# RTB2k_Pattern_Gen_Adapter.net
KiCad netlist of a schematic drawn in Altium Designer
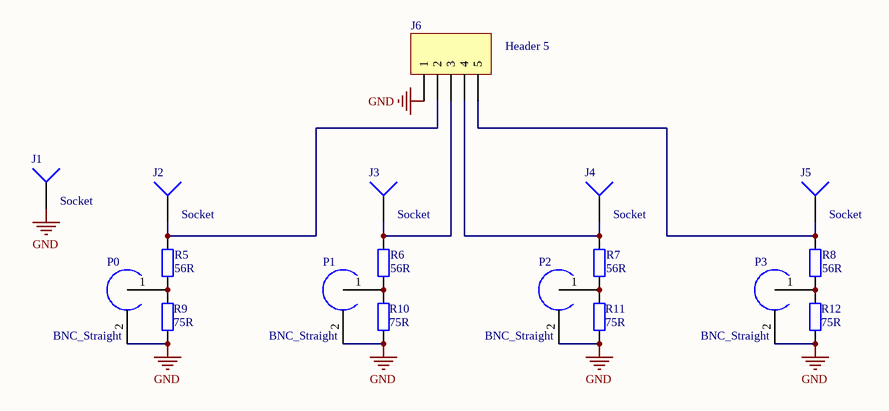
[diagram p0: RTB2k Pattern Gen Adapter.SchDoc]

(export (version "E")
  (design (tool "Eeschema 10.0.6"))
  (components
    (comp (ref "J1")
      (value "Socket")
      (footprint "PIN1")
      (fields (field (name "PUBLISHER") "Altium Limited"))
      (libsource (lib "Miscellaneous Connectors") (part "Socket"))
    )
    (comp (ref "J2")
      (value "Socket")
      (footprint "PIN1")
      (fields (field (name "PUBLISHER") "Altium Limited"))
      (libsource (lib "Miscellaneous Connectors") (part "Socket"))
    )
    (comp (ref "J3")
      (value "Socket")
      (footprint "PIN1")
      (fields (field (name "PUBLISHER") "Altium Limited"))
      (libsource (lib "Miscellaneous Connectors") (part "Socket"))
    )
    (comp (ref "J4")
      (value "Socket")
      (footprint "PIN1")
      (fields (field (name "PUBLISHER") "Altium Limited"))
      (libsource (lib "Miscellaneous Connectors") (part "Socket"))
    )
    (comp (ref "J5")
      (value "Socket")
      (footprint "PIN1")
      (fields (field (name "PUBLISHER") "Altium Limited"))
      (libsource (lib "Miscellaneous Connectors") (part "Socket"))
    )
    (comp (ref "J6")
      (value "Header 5")
      (footprint "HDR1X5")
      (description "Header, 5-Pin")
      (fields (field (name "PUBLISHER") "Altium Limited"))
      (libsource (lib "Miscellaneous Connectors") (part "Header 5"))
    )
    (comp (ref "P0")
      (value "BNC_Straight")
      (footprint "BNC_Straight")
      (description "BNC Connector (Straight)")
      (libsource (lib "TV_Altium_library") (part "BNC_Straight"))
    )
    (comp (ref "P1")
      (value "BNC_Straight")
      (footprint "BNC_Straight")
      (description "BNC Connector (Straight)")
      (libsource (lib "TV_Altium_library") (part "BNC_Straight"))
    )
    (comp (ref "P2")
      (value "BNC_Straight")
      (footprint "BNC_Straight")
      (description "BNC Connector (Straight)")
      (libsource (lib "TV_Altium_library") (part "BNC_Straight"))
    )
    (comp (ref "P3")
      (value "BNC_Straight")
      (footprint "BNC_Straight")
      (description "BNC Connector (Straight)")
      (libsource (lib "TV_Altium_library") (part "BNC_Straight"))
    )
    (comp (ref "R5")
      (value "56R")
      (footprint "0805R")
      (libsource (lib "TV_Altium_library") (part "Resistor"))
    )
    (comp (ref "R6")
      (value "56R")
      (footprint "0805R")
      (libsource (lib "TV_Altium_library") (part "Resistor"))
    )
    (comp (ref "R7")
      (value "56R")
      (footprint "0805R")
      (libsource (lib "TV_Altium_library") (part "Resistor"))
    )
    (comp (ref "R8")
      (value "56R")
      (footprint "0805R")
      (libsource (lib "TV_Altium_library") (part "Resistor"))
    )
    (comp (ref "R9") (value "75R") (footprint "0805R") (libsource (lib "") (part "Resistor_1")))
    (comp (ref "R10") (value "75R") (footprint "0805R") (libsource (lib "") (part "Resistor_1")))
    (comp (ref "R11") (value "75R") (footprint "0805R") (libsource (lib "") (part "Resistor_1")))
    (comp (ref "R12") (value "75R") (footprint "0805R") (libsource (lib "") (part "Resistor_1")))
  )
  (nets
    (net (code "1") (name "GND") (class "Default")
      (node (ref "J1") (pin "1") (pinfunction "1_1") (pintype "passive"))
      (node (ref "J6") (pin "1") (pinfunction "1_1") (pintype "passive"))
      (node (ref "P0") (pin "2") (pinfunction "Shield_2") (pintype "passive"))
      (node (ref "P1") (pin "2") (pinfunction "Shield_2") (pintype "passive"))
      (node (ref "P2") (pin "2") (pinfunction "Shield_2") (pintype "passive"))
      (node (ref "P3") (pin "2") (pinfunction "Shield_2") (pintype "passive"))
      (node (ref "R10") (pin "2") (pinfunction "2_2") (pintype "passive"))
      (node (ref "R11") (pin "2") (pinfunction "2_2") (pintype "passive"))
      (node (ref "R12") (pin "2") (pinfunction "2_2") (pintype "passive"))
      (node (ref "R9") (pin "2") (pinfunction "2_2") (pintype "passive"))
    )
    (net (code "2") (name "Net-(J2-Pad1)") (class "Default")
      (node (ref "J2") (pin "1") (pinfunction "1_1") (pintype "passive"))
      (node (ref "J6") (pin "2") (pinfunction "2_2") (pintype "passive"))
      (node (ref "R5") (pin "2") (pinfunction "2_2") (pintype "passive"))
    )
    (net (code "3") (name "Net-(J3-Pad1)") (class "Default")
      (node (ref "J3") (pin "1") (pinfunction "1_1") (pintype "passive"))
      (node (ref "J6") (pin "3") (pinfunction "3_3") (pintype "passive"))
      (node (ref "R6") (pin "2") (pinfunction "2_2") (pintype "passive"))
    )
    (net (code "4") (name "Net-(J4-Pad1)") (class "Default")
      (node (ref "J4") (pin "1") (pinfunction "1_1") (pintype "passive"))
      (node (ref "J6") (pin "4") (pinfunction "4_4") (pintype "passive"))
      (node (ref "R7") (pin "2") (pinfunction "2_2") (pintype "passive"))
    )
    (net (code "5") (name "Net-(J5-Pad1)") (class "Default")
      (node (ref "J5") (pin "1") (pinfunction "1_1") (pintype "passive"))
      (node (ref "J6") (pin "5") (pinfunction "5_5") (pintype "passive"))
      (node (ref "R8") (pin "2") (pinfunction "2_2") (pintype "passive"))
    )
    (net (code "6") (name "Net-(P0-Centre)") (class "Default")
      (node (ref "P0") (pin "1") (pinfunction "Centre_1") (pintype "passive"))
      (node (ref "R5") (pin "1") (pinfunction "1_1") (pintype "passive"))
      (node (ref "R9") (pin "1") (pinfunction "1_1") (pintype "passive"))
    )
    (net (code "7") (name "Net-(P1-Centre)") (class "Default")
      (node (ref "P1") (pin "1") (pinfunction "Centre_1") (pintype "passive"))
      (node (ref "R10") (pin "1") (pinfunction "1_1") (pintype "passive"))
      (node (ref "R6") (pin "1") (pinfunction "1_1") (pintype "passive"))
    )
    (net (code "8") (name "Net-(P2-Centre)") (class "Default")
      (node (ref "P2") (pin "1") (pinfunction "Centre_1") (pintype "passive"))
      (node (ref "R11") (pin "1") (pinfunction "1_1") (pintype "passive"))
      (node (ref "R7") (pin "1") (pinfunction "1_1") (pintype "passive"))
    )
    (net (code "9") (name "Net-(P3-Centre)") (class "Default")
      (node (ref "P3") (pin "1") (pinfunction "Centre_1") (pintype "passive"))
      (node (ref "R12") (pin "1") (pinfunction "1_1") (pintype "passive"))
      (node (ref "R8") (pin "1") (pinfunction "1_1") (pintype "passive"))
    )
  )
)
